# SlowDown_V1_0.net
KiCad netlist of a schematic drawn in Altium Designer
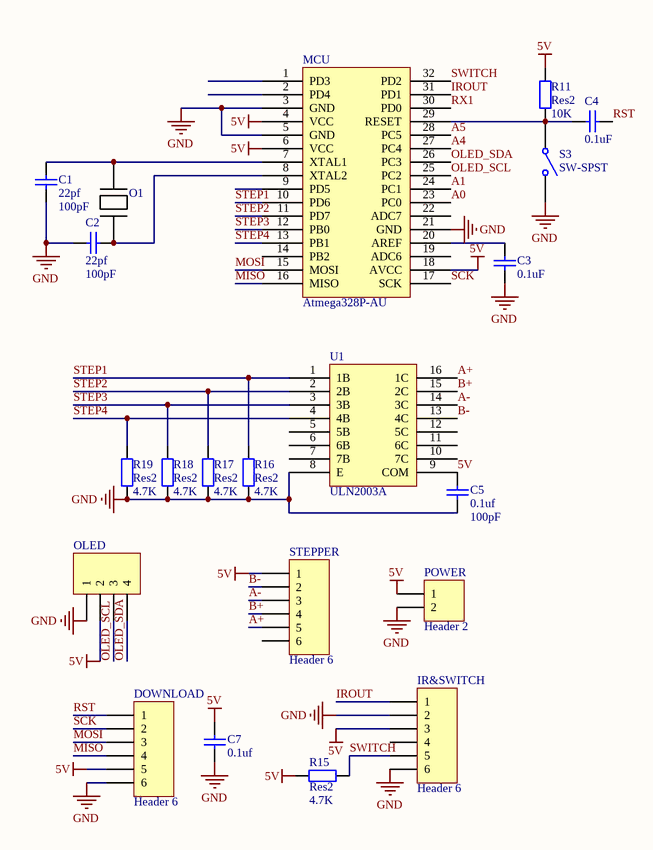
[diagram p0: SlowDown!V1.0.SchDoc]

(export (version "E")
  (design (tool "Eeschema 10.0.6"))
  (components
    (comp (ref "C1")
      (value "22pf")
      (footprint "0603Standard")
      (description "Capacitor")
      (fields (field (name "ALTIUM_VALUE") "100pF") (field (name "PUBLISHER") "Altium Limited"))
      (libsource (lib "Miscellaneous Devices") (part "Cap"))
    )
    (comp (ref "C2")
      (value "22pf")
      (footprint "0603Standard")
      (description "Capacitor")
      (fields (field (name "ALTIUM_VALUE") "100pF") (field (name "PUBLISHER") "Altium Limited"))
      (libsource (lib "Miscellaneous Devices") (part "Cap"))
    )
    (comp (ref "C3")
      (value "0.1uF")
      (footprint "0603Standard")
      (description "Capacitor")
      (libsource (lib "练手") (part "cap"))
    )
    (comp (ref "C4")
      (value "0.1uF")
      (footprint "0603Standard")
      (description "Capacitor")
      (libsource (lib "练手") (part "cap"))
    )
    (comp (ref "C5")
      (value "0.1uf")
      (footprint "0603Standard")
      (description "Capacitor")
      (fields (field (name "ALTIUM_VALUE") "100pF") (field (name "PUBLISHER") "Altium Limited"))
      (libsource (lib "Miscellaneous Devices") (part "Cap"))
    )
    (comp (ref "C7")
      (value "0.1uf")
      (footprint "0603Standard")
      (description "Capacitor")
      (fields (field (name "PUBLISHER") "Altium Limited"))
      (libsource (lib "Miscellaneous Devices") (part "Cap"))
    )
    (comp (ref "DOWNLOAD")
      (value "Header 6")
      (footprint "SH-6P")
      (description "Header, 6-Pin")
      (fields (field (name "PUBLISHER") "Altium Limited"))
      (libsource (lib "Miscellaneous Connectors") (part "Header 6"))
    )
    (comp (ref "IR&SWITCH")
      (value "Header 6")
      (footprint "SH-6P")
      (description "Header, 6-Pin")
      (fields (field (name "PUBLISHER") "Altium Limited"))
      (libsource (lib "Miscellaneous Connectors") (part "Header 6"))
    )
    (comp (ref "MCU")
      (value "Atmega328P-AU")
      (footprint "ATMega328P-AU")
      (libsource (lib "SlowDownLib") (part "Atmega328P-AU"))
    )
    (comp (ref "O1")
      (value "16M")
      (footprint "16MHZ20PF")
      (libsource (lib "SlowDownLib") (part "Crystal Osc 16M"))
    )
    (comp (ref "OLED")
      (value "Header 4")
      (footprint "SH-4P")
      (description "Header, 4-Pin")
      (fields (field (name "PUBLISHER") "Altium Limited"))
      (libsource (lib "Miscellaneous Connectors") (part "Header 4"))
    )
    (comp (ref "POWER")
      (value "Header 2")
      (footprint "HDR1X2")
      (description "Header, 2-Pin")
      (fields (field (name "PUBLISHER") "Altium Limited"))
      (libsource (lib "Miscellaneous Connectors") (part "Header 2"))
    )
    (comp (ref "R11")
      (value "Res2")
      (footprint "0603Standard")
      (description "Resistor")
      (fields (field (name "ALTIUM_VALUE") "10K") (field (name "PUBLISHER") "Altium Limited"))
      (libsource (lib "") (part "Res2_1"))
    )
    (comp (ref "R15")
      (value "Res2")
      (footprint "0603Standard")
      (description "Resistor")
      (fields (field (name "ALTIUM_VALUE") "4.7K") (field (name "PUBLISHER") "Altium Limited"))
      (libsource (lib "") (part "Res2_2"))
    )
    (comp (ref "R16")
      (value "Res2")
      (footprint "0603Standard")
      (description "Resistor")
      (fields (field (name "ALTIUM_VALUE") "4.7K") (field (name "PUBLISHER") "Altium Limited"))
      (libsource (lib "Miscellaneous Devices") (part "Res2"))
    )
    (comp (ref "R17")
      (value "Res2")
      (footprint "0603Standard")
      (description "Resistor")
      (fields (field (name "ALTIUM_VALUE") "4.7K") (field (name "PUBLISHER") "Altium Limited"))
      (libsource (lib "Miscellaneous Devices") (part "Res2"))
    )
    (comp (ref "R18")
      (value "Res2")
      (footprint "0603Standard")
      (description "Resistor")
      (fields (field (name "ALTIUM_VALUE") "4.7K") (field (name "PUBLISHER") "Altium Limited"))
      (libsource (lib "Miscellaneous Devices") (part "Res2"))
    )
    (comp (ref "R19")
      (value "Res2")
      (footprint "0603Standard")
      (description "Resistor")
      (fields (field (name "ALTIUM_VALUE") "4.7K") (field (name "PUBLISHER") "Altium Limited"))
      (libsource (lib "Miscellaneous Devices") (part "Res2"))
    )
    (comp (ref "S3")
      (value "SW-SPST")
      (footprint "BUTTOM")
      (description "Single-Pole, Single-Throw Switch")
      (fields (field (name "PUBLISHER") "Altium Limited"))
      (libsource (lib "Miscellaneous Devices") (part "SW-SPST"))
    )
    (comp (ref "STEPPER")
      (value "Header 6")
      (footprint "SH-6P")
      (description "Header, 6-Pin")
      (fields (field (name "PUBLISHER") "Altium Limited"))
      (libsource (lib "Miscellaneous Connectors") (part "Header 6"))
    )
    (comp (ref "U1")
      (value "ULN2003A")
      (footprint "ULN2003A_SOP16")
      (libsource (lib "UPS") (part "ULN2003A"))
    )
  )
  (nets
    (net (code "1") (name "/A+") (class "Default")
      (node (ref "STEPPER") (pin "5") (pinfunction "5_5") (pintype "passive"))
      (node (ref "U1") (pin "16") (pinfunction "1C_16") (pintype "passive"))
    )
    (net (code "2") (name "/A-") (class "Default")
      (node (ref "STEPPER") (pin "3") (pinfunction "3_3") (pintype "passive"))
      (node (ref "U1") (pin "14") (pinfunction "3C_14") (pintype "passive"))
    )
    (net (code "3") (name "/A0") (class "Default")
      (node (ref "MCU") (pin "23") (pinfunction "PC0_23") (pintype "passive"))
    )
    (net (code "4") (name "/A1") (class "Default")
      (node (ref "MCU") (pin "24") (pinfunction "PC1_24") (pintype "passive"))
    )
    (net (code "5") (name "/A4") (class "Default")
      (node (ref "MCU") (pin "27") (pinfunction "PC4_27") (pintype "passive"))
    )
    (net (code "6") (name "/A5") (class "Default")
      (node (ref "MCU") (pin "28") (pinfunction "PC5_28") (pintype "passive"))
    )
    (net (code "7") (name "/B+") (class "Default")
      (node (ref "STEPPER") (pin "4") (pinfunction "4_4") (pintype "passive"))
      (node (ref "U1") (pin "15") (pinfunction "2C_15") (pintype "passive"))
    )
    (net (code "8") (name "/B-") (class "Default")
      (node (ref "STEPPER") (pin "2") (pinfunction "2_2") (pintype "passive"))
      (node (ref "U1") (pin "13") (pinfunction "4C_13") (pintype "passive"))
    )
    (net (code "9") (name "/IROUT") (class "Default")
      (node (ref "IR&SWITCH") (pin "1") (pinfunction "1_1") (pintype "passive"))
      (node (ref "MCU") (pin "31") (pinfunction "PD1_31") (pintype "passive"))
    )
    (net (code "10") (name "/MISO") (class "Default")
      (node (ref "DOWNLOAD") (pin "4") (pinfunction "4_4") (pintype "passive"))
      (node (ref "MCU") (pin "16") (pinfunction "MISO_16") (pintype "passive"))
    )
    (net (code "11") (name "/MOSI") (class "Default")
      (node (ref "DOWNLOAD") (pin "3") (pinfunction "3_3") (pintype "passive"))
      (node (ref "MCU") (pin "15") (pinfunction "MOSI_15") (pintype "passive"))
    )
    (net (code "12") (name "/OLED_SCL") (class "Default")
      (node (ref "MCU") (pin "25") (pinfunction "PC2_25") (pintype "passive"))
      (node (ref "OLED") (pin "3") (pinfunction "3_3") (pintype "passive"))
    )
    (net (code "13") (name "/OLED_SDA") (class "Default")
      (node (ref "MCU") (pin "26") (pinfunction "PC3_26") (pintype "passive"))
      (node (ref "OLED") (pin "4") (pinfunction "4_4") (pintype "passive"))
    )
    (net (code "14") (name "/RST") (class "Default")
      (node (ref "C4") (pin "2") (pinfunction "2_2") (pintype "passive"))
      (node (ref "DOWNLOAD") (pin "1") (pinfunction "1_1") (pintype "passive"))
    )
    (net (code "15") (name "/RX1") (class "Default")
      (node (ref "MCU") (pin "30") (pinfunction "PD0_30") (pintype "passive"))
    )
    (net (code "16") (name "/SCK") (class "Default")
      (node (ref "DOWNLOAD") (pin "2") (pinfunction "2_2") (pintype "passive"))
      (node (ref "MCU") (pin "17") (pinfunction "SCK_17") (pintype "passive"))
    )
    (net (code "17") (name "/STEP1") (class "Default")
      (node (ref "MCU") (pin "10") (pinfunction "PD6_10") (pintype "passive"))
      (node (ref "R16") (pin "2") (pinfunction "2_2") (pintype "passive"))
      (node (ref "U1") (pin "1") (pinfunction "1B_1") (pintype "passive"))
    )
    (net (code "18") (name "/STEP2") (class "Default")
      (node (ref "MCU") (pin "11") (pinfunction "PD7_11") (pintype "passive"))
      (node (ref "R17") (pin "2") (pinfunction "2_2") (pintype "passive"))
      (node (ref "U1") (pin "2") (pinfunction "2B_2") (pintype "passive"))
    )
    (net (code "19") (name "/STEP3") (class "Default")
      (node (ref "MCU") (pin "12") (pinfunction "PB0_12") (pintype "passive"))
      (node (ref "R18") (pin "2") (pinfunction "2_2") (pintype "passive"))
      (node (ref "U1") (pin "3") (pinfunction "3B_3") (pintype "passive"))
    )
    (net (code "20") (name "/STEP4") (class "Default")
      (node (ref "MCU") (pin "13") (pinfunction "PB1_13") (pintype "passive"))
      (node (ref "R19") (pin "2") (pinfunction "2_2") (pintype "passive"))
      (node (ref "U1") (pin "4") (pinfunction "4B_4") (pintype "passive"))
    )
    (net (code "21") (name "/SWITCH") (class "Default")
      (node (ref "IR&SWITCH") (pin "5") (pinfunction "5_5") (pintype "passive"))
      (node (ref "MCU") (pin "32") (pinfunction "PD2_32") (pintype "passive"))
      (node (ref "R15") (pin "1") (pinfunction "1_1") (pintype "passive"))
    )
    (net (code "22") (name "5V") (class "Default")
      (node (ref "C5") (pin "1") (pinfunction "1_1") (pintype "passive"))
      (node (ref "C7") (pin "1") (pinfunction "1_1") (pintype "passive"))
      (node (ref "DOWNLOAD") (pin "5") (pinfunction "5_5") (pintype "passive"))
      (node (ref "IR&SWITCH") (pin "3") (pinfunction "3_3") (pintype "passive"))
      (node (ref "MCU") (pin "18") (pinfunction "AVCC_18") (pintype "passive"))
      (node (ref "MCU") (pin "4") (pinfunction "VCC_4") (pintype "passive"))
      (node (ref "MCU") (pin "6") (pinfunction "VCC_6") (pintype "passive"))
      (node (ref "OLED") (pin "2") (pinfunction "2_2") (pintype "passive"))
      (node (ref "POWER") (pin "1") (pinfunction "1_1") (pintype "passive"))
      (node (ref "R11") (pin "1") (pinfunction "1_1") (pintype "passive"))
      (node (ref "R15") (pin "2") (pinfunction "2_2") (pintype "passive"))
      (node (ref "STEPPER") (pin "1") (pinfunction "1_1") (pintype "passive"))
      (node (ref "U1") (pin "9") (pinfunction "COM_9") (pintype "passive"))
    )
    (net (code "23") (name "GND") (class "Default")
      (node (ref "C1") (pin "1") (pinfunction "1_1") (pintype "passive"))
      (node (ref "C2") (pin "1") (pinfunction "1_1") (pintype "passive"))
      (node (ref "C3") (pin "1") (pinfunction "1_1") (pintype "passive"))
      (node (ref "C5") (pin "2") (pinfunction "2_2") (pintype "passive"))
      (node (ref "C7") (pin "2") (pinfunction "2_2") (pintype "passive"))
      (node (ref "DOWNLOAD") (pin "6") (pinfunction "6_6") (pintype "passive"))
      (node (ref "IR&SWITCH") (pin "2") (pinfunction "2_2") (pintype "passive"))
      (node (ref "IR&SWITCH") (pin "6") (pinfunction "6_6") (pintype "passive"))
      (node (ref "MCU") (pin "21") (pinfunction "GND_21") (pintype "passive"))
      (node (ref "MCU") (pin "3") (pinfunction "GND_3") (pintype "passive"))
      (node (ref "MCU") (pin "5") (pinfunction "GND_5") (pintype "passive"))
      (node (ref "OLED") (pin "1") (pinfunction "1_1") (pintype "passive"))
      (node (ref "POWER") (pin "2") (pinfunction "2_2") (pintype "passive"))
      (node (ref "R16") (pin "1") (pinfunction "1_1") (pintype "passive"))
      (node (ref "R17") (pin "1") (pinfunction "1_1") (pintype "passive"))
      (node (ref "R18") (pin "1") (pinfunction "1_1") (pintype "passive"))
      (node (ref "R19") (pin "1") (pinfunction "1_1") (pintype "passive"))
      (node (ref "S3") (pin "2") (pinfunction "NO_2") (pintype "passive"))
      (node (ref "U1") (pin "8") (pinfunction "E_8") (pintype "power_in"))
    )
    (net (code "24") (name "Net-(MCU-AREF)") (class "Default")
      (node (ref "C3") (pin "2") (pinfunction "2_2") (pintype "passive"))
      (node (ref "MCU") (pin "20") (pinfunction "AREF_20") (pintype "passive"))
    )
    (net (code "25") (name "Net-(MCU-RESET)") (class "Default")
      (node (ref "C4") (pin "1") (pinfunction "1_1") (pintype "passive"))
      (node (ref "MCU") (pin "29") (pinfunction "RESET_29") (pintype "passive"))
      (node (ref "R11") (pin "2") (pinfunction "2_2") (pintype "passive"))
      (node (ref "S3") (pin "1") (pinfunction "COMMON_1") (pintype "passive"))
    )
    (net (code "26") (name "Net-(MCU-XTAL1)") (class "Default")
      (node (ref "C1") (pin "2") (pinfunction "2_2") (pintype "passive"))
      (node (ref "MCU") (pin "7") (pinfunction "XTAL1_7") (pintype "passive"))
      (node (ref "O1") (pin "2") (pinfunction "2_2") (pintype "passive"))
    )
    (net (code "27") (name "Net-(MCU-XTAL2)") (class "Default")
      (node (ref "C2") (pin "2") (pinfunction "2_2") (pintype "passive"))
      (node (ref "MCU") (pin "8") (pinfunction "XTAL2_8") (pintype "passive"))
      (node (ref "O1") (pin "1") (pinfunction "1_1") (pintype "passive"))
    )
    (net (code "28") (name "unconnected-(IR&SWITCH-Pad4)") (class "Default")
      (node (ref "IR&SWITCH") (pin "4") (pinfunction "4_4") (pintype "passive"))
    )
    (net (code "29") (name "unconnected-(MCU-ADC6-Pad19)") (class "Default")
      (node (ref "MCU") (pin "19") (pinfunction "ADC6_19") (pintype "passive"))
    )
    (net (code "30") (name "unconnected-(MCU-ADC7-Pad22)") (class "Default")
      (node (ref "MCU") (pin "22") (pinfunction "ADC7_22") (pintype "passive"))
    )
    (net (code "31") (name "unconnected-(MCU-PB2-Pad14)") (class "Default")
      (node (ref "MCU") (pin "14") (pinfunction "PB2_14") (pintype "passive"))
    )
    (net (code "32") (name "unconnected-(MCU-PD3-Pad1)") (class "Default")
      (node (ref "MCU") (pin "1") (pinfunction "PD3_1") (pintype "passive"))
    )
    (net (code "33") (name "unconnected-(MCU-PD4-Pad2)") (class "Default")
      (node (ref "MCU") (pin "2") (pinfunction "PD4_2") (pintype "passive"))
    )
    (net (code "34") (name "unconnected-(MCU-PD5-Pad9)") (class "Default")
      (node (ref "MCU") (pin "9") (pinfunction "PD5_9") (pintype "passive"))
    )
    (net (code "35") (name "unconnected-(STEPPER-Pad6)") (class "Default")
      (node (ref "STEPPER") (pin "6") (pinfunction "6_6") (pintype "passive"))
    )
    (net (code "36") (name "unconnected-(U1-5B-Pad5)") (class "Default")
      (node (ref "U1") (pin "5") (pinfunction "5B_5") (pintype "passive"))
    )
    (net (code "37") (name "unconnected-(U1-5C-Pad12)") (class "Default")
      (node (ref "U1") (pin "12") (pinfunction "5C_12") (pintype "passive"))
    )
    (net (code "38") (name "unconnected-(U1-6B-Pad6)") (class "Default")
      (node (ref "U1") (pin "6") (pinfunction "6B_6") (pintype "passive"))
    )
    (net (code "39") (name "unconnected-(U1-6C-Pad11)") (class "Default")
      (node (ref "U1") (pin "11") (pinfunction "6C_11") (pintype "passive"))
    )
    (net (code "40") (name "unconnected-(U1-7B-Pad7)") (class "Default")
      (node (ref "U1") (pin "7") (pinfunction "7B_7") (pintype "passive"))
    )
    (net (code "41") (name "unconnected-(U1-7C-Pad10)") (class "Default")
      (node (ref "U1") (pin "10") (pinfunction "7C_10") (pintype "passive"))
    )
  )
)
